# 5_AudioIO.net
KiCad netlist of a schematic drawn in Altium Designer
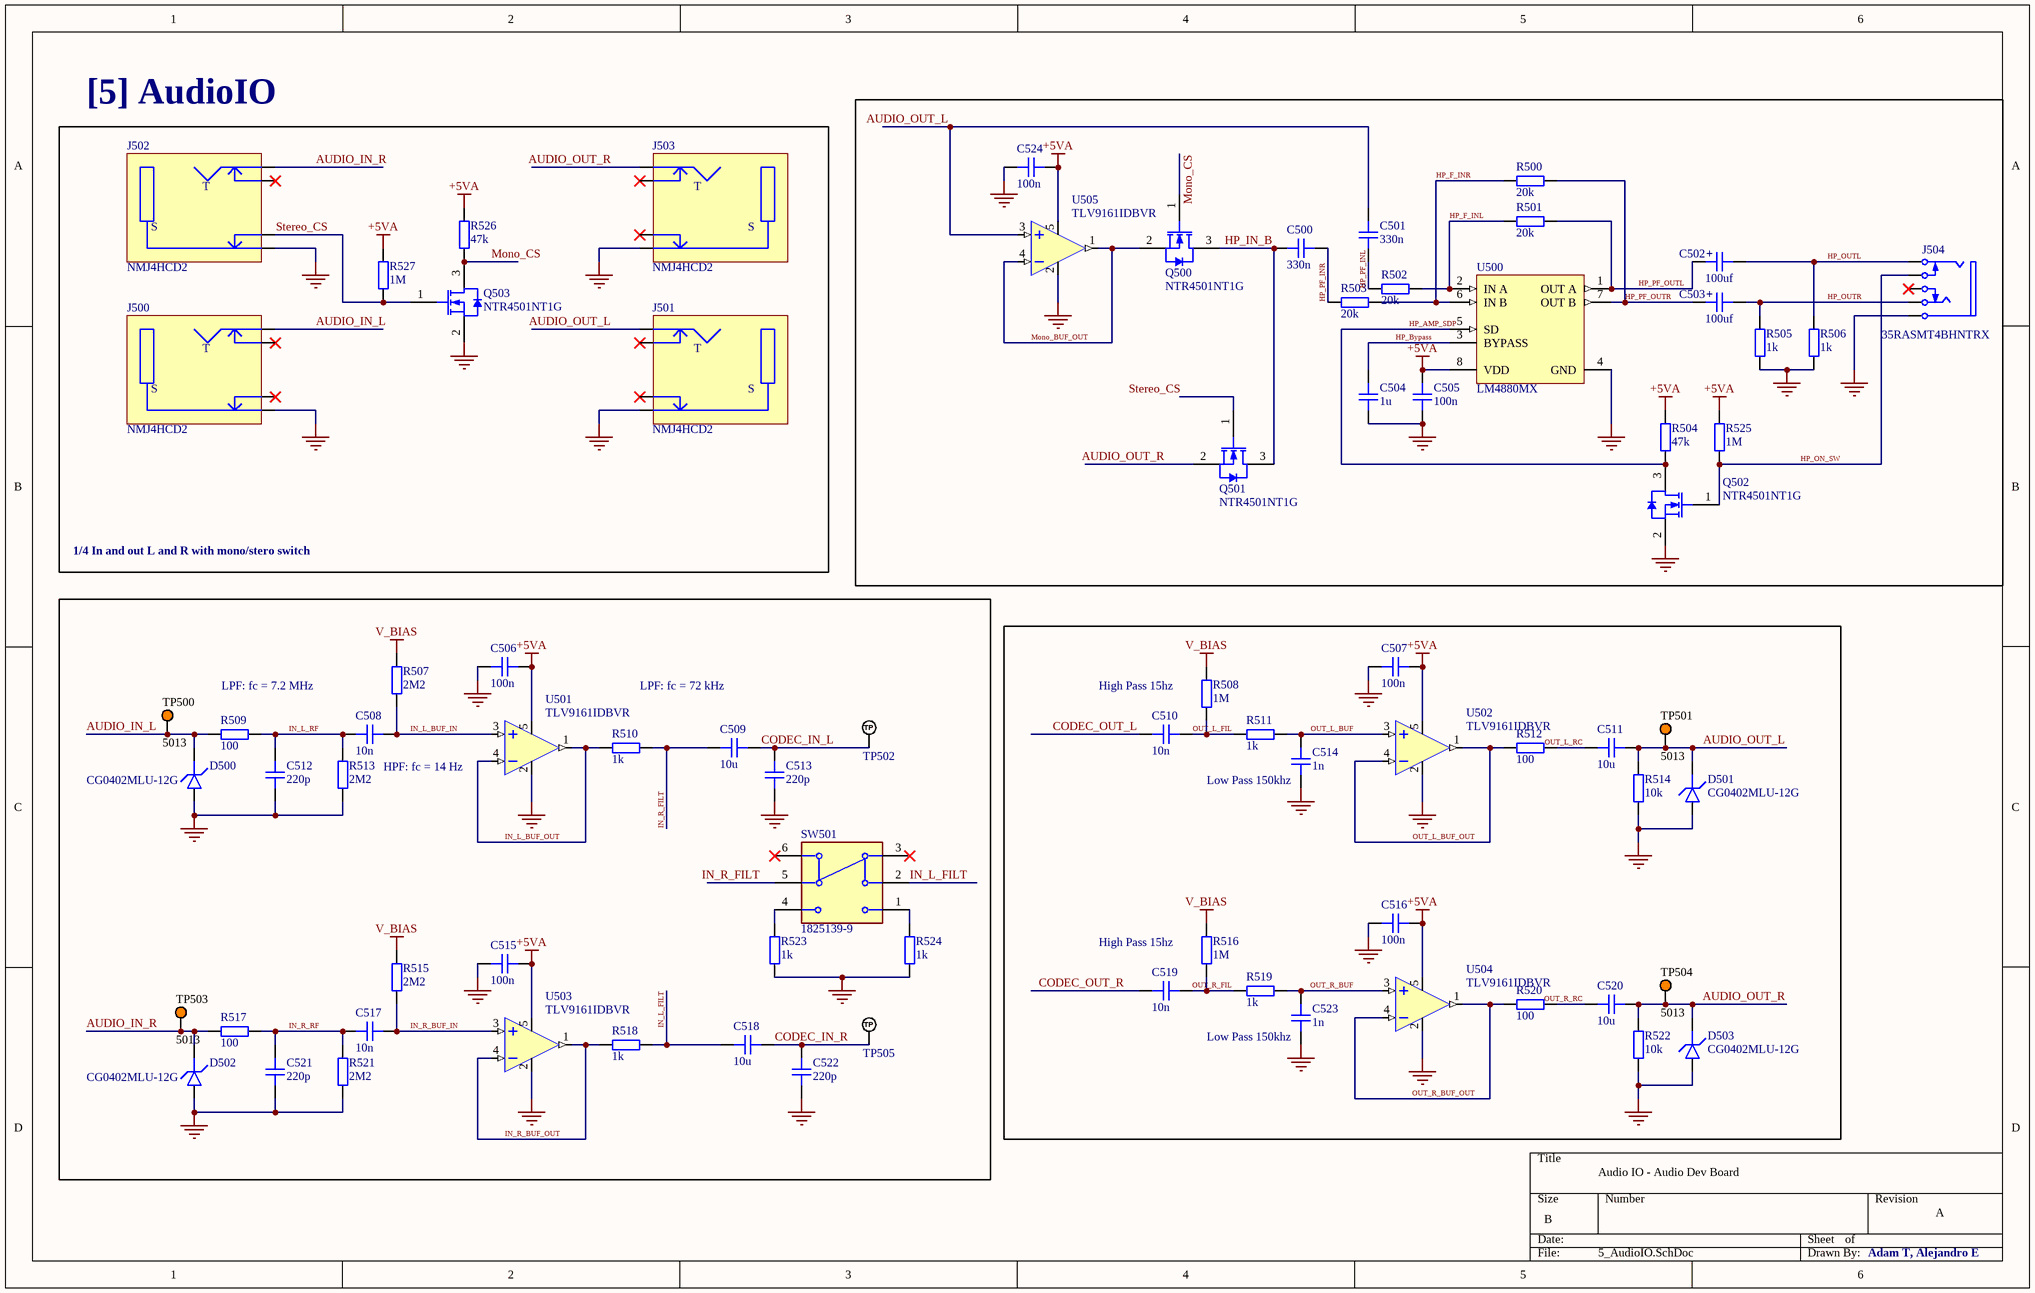
[diagram p0: 5_AudioIO.SchDoc]

(export (version "E")
  (design (tool "Eeschema 10.0.6"))
  (components
    (comp (ref "C500")
      (value "330n")
      (footprint "CAP_0603")
      (description "Capacitor SMD 0603")
      (libsource (lib "Schematic-Lib-PhilsLab") (part "CAP_0603"))
    )
    (comp (ref "C501")
      (value "330n")
      (footprint "CAP_0603")
      (description "Capacitor SMD 0603")
      (libsource (lib "Schematic-Lib-PhilsLab") (part "CAP_0603"))
    )
    (comp (ref "C502")
      (value "100uf")
      (footprint "CAP_AE_SMD_D6MM3_H5M55")
      (description "Capacitor SMD Aluminium Electrolytic 6.3mm Diameter 5.5mm Height\r\nRVT1C101M0605\r\nC37308")
      (libsource (lib "Schematic-Lib-PhilsLab") (part "CAP_ALEL_6.3x5.5"))
    )
    (comp (ref "C503")
      (value "100uf")
      (footprint "CAP_AE_SMD_D6MM3_H5M55")
      (description "Capacitor SMD Aluminium Electrolytic 6.3mm Diameter 5.5mm Height\r\nRVT1C101M0605\r\nC37308")
      (libsource (lib "Schematic-Lib-PhilsLab") (part "CAP_ALEL_6.3x5.5"))
    )
    (comp (ref "C504")
      (value "1u")
      (footprint "CAP_0603")
      (description "Capacitor SMD 0603")
      (libsource (lib "Schematic-Lib-PhilsLab") (part "CAP_0603"))
    )
    (comp (ref "C505")
      (value "100n")
      (footprint "CAP_0402")
      (description "Capacitor SMD 0402")
      (libsource (lib "Schematic-Lib-PhilsLab") (part "CAP_0402"))
    )
    (comp (ref "C506")
      (value "100n")
      (footprint "CAP_0402")
      (description "Capacitor SMD 0402")
      (libsource (lib "Schematic-Lib-PhilsLab") (part "CAP_0402"))
    )
    (comp (ref "C507")
      (value "100n")
      (footprint "CAP_0402")
      (description "Capacitor SMD 0402")
      (libsource (lib "Schematic-Lib-PhilsLab") (part "CAP_0402"))
    )
    (comp (ref "C508")
      (value "10n")
      (footprint "CAP_0402")
      (description "Capacitor SMD 0402")
      (libsource (lib "Schematic-Lib-PhilsLab") (part "CAP_0402"))
    )
    (comp (ref "C509")
      (value "10u")
      (footprint "CAP_0603")
      (description "Capacitor SMD 0603")
      (libsource (lib "Schematic-Lib-PhilsLab") (part "CAP_0603"))
    )
    (comp (ref "C510")
      (value "10n")
      (footprint "CAP_0402")
      (description "Capacitor SMD 0402")
      (libsource (lib "Schematic-Lib-PhilsLab") (part "CAP_0402"))
    )
    (comp (ref "C511")
      (value "10u")
      (footprint "CAP_0603")
      (description "Capacitor SMD 0603")
      (libsource (lib "Schematic-Lib-PhilsLab") (part "CAP_0603"))
    )
    (comp (ref "C512")
      (value "220p")
      (footprint "CAP_0402")
      (description "Capacitor SMD 0402")
      (libsource (lib "Schematic-Lib-PhilsLab") (part "CAP_0402"))
    )
    (comp (ref "C513")
      (value "220p")
      (footprint "CAP_0402")
      (description "Capacitor SMD 0402")
      (libsource (lib "Schematic-Lib-PhilsLab") (part "CAP_0402"))
    )
    (comp (ref "C514")
      (value "1n")
      (footprint "CAP_0402")
      (description "Capacitor SMD 0402")
      (libsource (lib "Schematic-Lib-PhilsLab") (part "CAP_0402"))
    )
    (comp (ref "C515")
      (value "100n")
      (footprint "CAP_0402")
      (description "Capacitor SMD 0402")
      (libsource (lib "Schematic-Lib-PhilsLab") (part "CAP_0402"))
    )
    (comp (ref "C516")
      (value "100n")
      (footprint "CAP_0402")
      (description "Capacitor SMD 0402")
      (libsource (lib "Schematic-Lib-PhilsLab") (part "CAP_0402"))
    )
    (comp (ref "C517")
      (value "10n")
      (footprint "CAP_0402")
      (description "Capacitor SMD 0402")
      (libsource (lib "Schematic-Lib-PhilsLab") (part "CAP_0402"))
    )
    (comp (ref "C518")
      (value "10u")
      (footprint "CAP_0603")
      (description "Capacitor SMD 0603")
      (libsource (lib "Schematic-Lib-PhilsLab") (part "CAP_0603"))
    )
    (comp (ref "C519")
      (value "10n")
      (footprint "CAP_0402")
      (description "Capacitor SMD 0402")
      (libsource (lib "Schematic-Lib-PhilsLab") (part "CAP_0402"))
    )
    (comp (ref "C520")
      (value "10u")
      (footprint "CAP_0603")
      (description "Capacitor SMD 0603")
      (libsource (lib "Schematic-Lib-PhilsLab") (part "CAP_0603"))
    )
    (comp (ref "C521")
      (value "220p")
      (footprint "CAP_0402")
      (description "Capacitor SMD 0402")
      (libsource (lib "Schematic-Lib-PhilsLab") (part "CAP_0402"))
    )
    (comp (ref "C522")
      (value "220p")
      (footprint "CAP_0402")
      (description "Capacitor SMD 0402")
      (libsource (lib "Schematic-Lib-PhilsLab") (part "CAP_0402"))
    )
    (comp (ref "C523")
      (value "1n")
      (footprint "CAP_0402")
      (description "Capacitor SMD 0402")
      (libsource (lib "Schematic-Lib-PhilsLab") (part "CAP_0402"))
    )
    (comp (ref "C524")
      (value "100n")
      (footprint "CAP_0402")
      (description "Capacitor SMD 0402")
      (libsource (lib "Schematic-Lib-PhilsLab") (part "CAP_0402"))
    )
    (comp (ref "D500")
      (value "CG0402MLU-12G")
      (footprint "D_0402")
      (description "Diode TVS / ESD 0402")
      (libsource (lib "Schematic-Lib-PhilsLab") (part "D_TVS_0402"))
    )
    (comp (ref "D501")
      (value "CG0402MLU-12G")
      (footprint "D_0402")
      (description "Diode TVS / ESD 0402")
      (libsource (lib "Schematic-Lib-PhilsLab") (part "D_TVS_0402"))
    )
    (comp (ref "D502")
      (value "CG0402MLU-12G")
      (footprint "D_0402")
      (description "Diode TVS / ESD 0402")
      (libsource (lib "Schematic-Lib-PhilsLab") (part "D_TVS_0402"))
    )
    (comp (ref "D503")
      (value "CG0402MLU-12G")
      (footprint "D_0402")
      (description "Diode TVS / ESD 0402")
      (libsource (lib "Schematic-Lib-PhilsLab") (part "D_TVS_0402"))
    )
    (comp (ref "J500")
      (value "NMJ4HCD2")
      (footprint "NMJ4HCD2")
      (description "1/4\" Mono Jack, TS Switched")
      (fields (field (name "MANUFACTURER") "Neutrik"))
      (libsource (lib "") (part "NMJ4HCD2_1"))
    )
    (comp (ref "J501")
      (value "NMJ4HCD2")
      (footprint "NMJ4HCD2")
      (description "1/4\" Mono Jack, TS Switched")
      (fields (field (name "MANUFACTURER") "Neutrik"))
      (libsource (lib "Schematic-Lib-PhilsLab") (part "NMJ4HCD2"))
    )
    (comp (ref "J502")
      (value "NMJ4HCD2")
      (footprint "NMJ4HCD2")
      (description "1/4\" Mono Jack, TS Switched")
      (fields (field (name "MANUFACTURER") "Neutrik"))
      (libsource (lib "") (part "NMJ4HCD2_1"))
    )
    (comp (ref "J503")
      (value "NMJ4HCD2")
      (footprint "NMJ4HCD2")
      (description "1/4\" Mono Jack, TS Switched")
      (fields (field (name "MANUFACTURER") "Neutrik"))
      (libsource (lib "Schematic-Lib-PhilsLab") (part "NMJ4HCD2"))
    )
    (comp (ref "J504")
      (value "35RASMT4BHNTRX")
      (footprint "SWIT-35RASMT4BHNTRX_V")
      (description "Female 3.5 mm Phone Jack, 5 Position, Height 5 mm, RoHS, Tape and Reel")
      (libsource (lib "Altium Content Vault") (part "JACK-3CD5-RN"))
    )
    (comp (ref "Q500")
      (value "NTR4501NT1G")
      (footprint "ONSC-SOT-23-3-318-08_V")
      (description "Power MOSFET, 20 V, 3.2 A, Single N-Channel, 3-Pin SOT-23, Pb-Free, Tape and Reel")
      (fields (field (name "MANUFACTURER") "On Semiconductor"))
      (libsource (lib "Altium Content Vault") (part "ONSC-NMOS-G1S2D3-3"))
    )
    (comp (ref "Q501")
      (value "NTR4501NT1G")
      (footprint "ONSC-SOT-23-3-318-08_V")
      (description "Power MOSFET, 20 V, 3.2 A, Single N-Channel, 3-Pin SOT-23, Pb-Free, Tape and Reel")
      (fields (field (name "MANUFACTURER") "On Semiconductor"))
      (libsource (lib "Altium Content Vault") (part "ONSC-NMOS-G1S2D3-3"))
    )
    (comp (ref "Q502")
      (value "NTR4501NT1G")
      (footprint "ONSC-SOT-23-3-318-08_V")
      (description "Power MOSFET, 20 V, 3.2 A, Single N-Channel, 3-Pin SOT-23, Pb-Free, Tape and Reel")
      (fields (field (name "MANUFACTURER") "On Semiconductor"))
      (libsource (lib "Altium Content Vault") (part "ONSC-NMOS-G1S2D3-3"))
    )
    (comp (ref "Q503")
      (value "NTR4501NT1G")
      (footprint "ONSC-SOT-23-3-318-08_V")
      (description "Power MOSFET, 20 V, 3.2 A, Single N-Channel, 3-Pin SOT-23, Pb-Free, Tape and Reel")
      (fields (field (name "MANUFACTURER") "On Semiconductor"))
      (libsource (lib "Altium Content Vault") (part "ONSC-NMOS-G1S2D3-3"))
    )
    (comp (ref "R500")
      (value "20k")
      (footprint "RES_0402")
      (description "Resistor SMD 0402")
      (libsource (lib "Schematic-Lib-PhilsLab") (part "RES_0402"))
    )
    (comp (ref "R501")
      (value "20k")
      (footprint "RES_0402")
      (description "Resistor SMD 0402")
      (libsource (lib "Schematic-Lib-PhilsLab") (part "RES_0402"))
    )
    (comp (ref "R502")
      (value "20k")
      (footprint "RES_0402")
      (description "Resistor SMD 0402")
      (libsource (lib "Schematic-Lib-PhilsLab") (part "RES_0402"))
    )
    (comp (ref "R503")
      (value "20k")
      (footprint "RES_0402")
      (description "Resistor SMD 0402")
      (libsource (lib "Schematic-Lib-PhilsLab") (part "RES_0402"))
    )
    (comp (ref "R504")
      (value "47k")
      (footprint "RES_0402")
      (description "Resistor SMD 0402")
      (libsource (lib "Schematic-Lib-PhilsLab") (part "RES_0402"))
    )
    (comp (ref "R505")
      (value "1k")
      (footprint "RES_0402")
      (description "Resistor SMD 0402")
      (libsource (lib "Schematic-Lib-PhilsLab") (part "RES_0402"))
    )
    (comp (ref "R506")
      (value "1k")
      (footprint "RES_0402")
      (description "Resistor SMD 0402")
      (libsource (lib "Schematic-Lib-PhilsLab") (part "RES_0402"))
    )
    (comp (ref "R507")
      (value "2M2")
      (footprint "RES_0402")
      (description "Resistor SMD 0402")
      (libsource (lib "Schematic-Lib-PhilsLab") (part "RES_0402"))
    )
    (comp (ref "R508")
      (value "1M")
      (footprint "RES_0402")
      (description "Resistor SMD 0402")
      (libsource (lib "Schematic-Lib-PhilsLab") (part "RES_0402"))
    )
    (comp (ref "R509")
      (value "100")
      (footprint "RES_0402")
      (description "Resistor SMD 0402")
      (libsource (lib "Schematic-Lib-PhilsLab") (part "RES_0402"))
    )
    (comp (ref "R510")
      (value "1k")
      (footprint "RES_0402")
      (description "Resistor SMD 0402")
      (libsource (lib "Schematic-Lib-PhilsLab") (part "RES_0402"))
    )
    (comp (ref "R511")
      (value "1k")
      (footprint "RES_0402")
      (description "Resistor SMD 0402")
      (libsource (lib "Schematic-Lib-PhilsLab") (part "RES_0402"))
    )
    (comp (ref "R512")
      (value "100")
      (footprint "RES_0402")
      (description "Resistor SMD 0402")
      (libsource (lib "Schematic-Lib-PhilsLab") (part "RES_0402"))
    )
    (comp (ref "R513")
      (value "2M2")
      (footprint "RES_0402")
      (description "Resistor SMD 0402")
      (libsource (lib "Schematic-Lib-PhilsLab") (part "RES_0402"))
    )
    (comp (ref "R514")
      (value "10k")
      (footprint "RES_0402")
      (description "Resistor SMD 0402")
      (libsource (lib "Schematic-Lib-PhilsLab") (part "RES_0402"))
    )
    (comp (ref "R515")
      (value "2M2")
      (footprint "RES_0402")
      (description "Resistor SMD 0402")
      (libsource (lib "Schematic-Lib-PhilsLab") (part "RES_0402"))
    )
    (comp (ref "R516")
      (value "1M")
      (footprint "RES_0402")
      (description "Resistor SMD 0402")
      (libsource (lib "Schematic-Lib-PhilsLab") (part "RES_0402"))
    )
    (comp (ref "R517")
      (value "100")
      (footprint "RES_0402")
      (description "Resistor SMD 0402")
      (libsource (lib "Schematic-Lib-PhilsLab") (part "RES_0402"))
    )
    (comp (ref "R518")
      (value "1k")
      (footprint "RES_0402")
      (description "Resistor SMD 0402")
      (libsource (lib "Schematic-Lib-PhilsLab") (part "RES_0402"))
    )
    (comp (ref "R519")
      (value "1k")
      (footprint "RES_0402")
      (description "Resistor SMD 0402")
      (libsource (lib "Schematic-Lib-PhilsLab") (part "RES_0402"))
    )
    (comp (ref "R520")
      (value "100")
      (footprint "RES_0402")
      (description "Resistor SMD 0402")
      (libsource (lib "Schematic-Lib-PhilsLab") (part "RES_0402"))
    )
    (comp (ref "R521")
      (value "2M2")
      (footprint "RES_0402")
      (description "Resistor SMD 0402")
      (libsource (lib "Schematic-Lib-PhilsLab") (part "RES_0402"))
    )
    (comp (ref "R522")
      (value "10k")
      (footprint "RES_0402")
      (description "Resistor SMD 0402")
      (libsource (lib "Schematic-Lib-PhilsLab") (part "RES_0402"))
    )
    (comp (ref "R523")
      (value "1k")
      (footprint "RES_0402")
      (description "Resistor SMD 0402")
      (libsource (lib "Schematic-Lib-PhilsLab") (part "RES_0402"))
    )
    (comp (ref "R524")
      (value "1k")
      (footprint "RES_0402")
      (description "Resistor SMD 0402")
      (libsource (lib "Schematic-Lib-PhilsLab") (part "RES_0402"))
    )
    (comp (ref "R525")
      (value "1M")
      (footprint "RES_0402")
      (description "Resistor SMD 0402")
      (libsource (lib "Schematic-Lib-PhilsLab") (part "RES_0402"))
    )
    (comp (ref "R526")
      (value "47k")
      (footprint "RES_0402")
      (description "Resistor SMD 0402")
      (libsource (lib "Schematic-Lib-PhilsLab") (part "RES_0402"))
    )
    (comp (ref "R527")
      (value "1M")
      (footprint "RES_0402")
      (description "Resistor SMD 0402")
      (libsource (lib "Schematic-Lib-PhilsLab") (part "RES_0402"))
    )
    (comp (ref "SW501")
      (value "1825139-9")
      (footprint "FP-1825139-9-MFG")
      (description "SWITCH TOGGLE DPDT 5A 120V")
      (libsource (lib "Altium Content Vault") (part "51a017c41a8b71834c976c69ad17c94"))
    )
    (comp (ref "TP500")
      (value "5013")
      (footprint "KSTN-5013_V")
      (description "Test Point, Orange, Through Hole, RoHS, Bulk")
      (fields (field (name "MANUFACTURER") "Keystone"))
      (libsource (lib "Altium Content Vault") (part "TESTPOINT_ORANGE"))
    )
    (comp (ref "TP501")
      (value "5013")
      (footprint "KSTN-5013_V")
      (description "Test Point, Orange, Through Hole, RoHS, Bulk")
      (fields (field (name "MANUFACTURER") "Keystone"))
      (libsource (lib "Altium Content Vault") (part "TESTPOINT_ORANGE"))
    )
    (comp (ref "TP502")
      (value "TP_NOBOM")
      (footprint "PAD_RND_1MM")
      (description "Test Point Round 1mm (NO BOM)")
      (libsource (lib "Schematic-Lib-PhilsLab") (part "TEST_POINT_RND_1MM"))
    )
    (comp (ref "TP503")
      (value "5013")
      (footprint "KSTN-5013_V")
      (description "Test Point, Orange, Through Hole, RoHS, Bulk")
      (fields (field (name "MANUFACTURER") "Keystone"))
      (libsource (lib "Altium Content Vault") (part "TESTPOINT_ORANGE"))
    )
    (comp (ref "TP504")
      (value "5013")
      (footprint "KSTN-5013_V")
      (description "Test Point, Orange, Through Hole, RoHS, Bulk")
      (fields (field (name "MANUFACTURER") "Keystone"))
      (libsource (lib "Altium Content Vault") (part "TESTPOINT_ORANGE"))
    )
    (comp (ref "TP505")
      (value "TP_NOBOM")
      (footprint "PAD_RND_1MM")
      (description "Test Point Round 1mm (NO BOM)")
      (libsource (lib "Schematic-Lib-PhilsLab") (part "TEST_POINT_RND_1MM"))
    )
    (comp (ref "U500")
      (value "LM4880MX")
      (footprint "M08A_L")
      (description "Dual 200mW Audio Power Amplifier with Shutdown Mode, 8-pin Narrow SOIC")
      (fields (field (name "MANUFACTURER") "National Semiconductor"))
      (libsource (lib "Altium Content Vault") (part "AMP-APA-LM4880-8"))
    )
    (comp (ref "U501")
      (value "TLV9161IDBVR")
      (footprint "SOT-23-5")
      (description "TLV916x 16-V, 11-MHz, Rail-to-Rail Input/Output, Low Offset Voltage, Low Noise Op Amp SOT-23-5")
      (fields (field (name "MANUFACTURER") "Texas Instruments"))
      (libsource (lib "Schematic-Lib-PhilsLab") (part "TLV9161IDBVR"))
    )
    (comp (ref "U502")
      (value "TLV9161IDBVR")
      (footprint "SOT-23-5")
      (description "TLV916x 16-V, 11-MHz, Rail-to-Rail Input/Output, Low Offset Voltage, Low Noise Op Amp SOT-23-5")
      (fields (field (name "MANUFACTURER") "Texas Instruments"))
      (libsource (lib "Schematic-Lib-PhilsLab") (part "TLV9161IDBVR"))
    )
    (comp (ref "U503")
      (value "TLV9161IDBVR")
      (footprint "SOT-23-5")
      (description "TLV916x 16-V, 11-MHz, Rail-to-Rail Input/Output, Low Offset Voltage, Low Noise Op Amp SOT-23-5")
      (fields (field (name "MANUFACTURER") "Texas Instruments"))
      (libsource (lib "Schematic-Lib-PhilsLab") (part "TLV9161IDBVR"))
    )
    (comp (ref "U504")
      (value "TLV9161IDBVR")
      (footprint "SOT-23-5")
      (description "TLV916x 16-V, 11-MHz, Rail-to-Rail Input/Output, Low Offset Voltage, Low Noise Op Amp SOT-23-5")
      (fields (field (name "MANUFACTURER") "Texas Instruments"))
      (libsource (lib "Schematic-Lib-PhilsLab") (part "TLV9161IDBVR"))
    )
    (comp (ref "U505")
      (value "TLV9161IDBVR")
      (footprint "SOT-23-5")
      (description "TLV916x 16-V, 11-MHz, Rail-to-Rail Input/Output, Low Offset Voltage, Low Noise Op Amp SOT-23-5")
      (fields (field (name "MANUFACTURER") "Texas Instruments"))
      (libsource (lib "Schematic-Lib-PhilsLab") (part "TLV9161IDBVR"))
    )
  )
  (nets
    (net (code "1") (name "+5VA") (class "Default")
      (node (ref "C505") (pin "2") (pinfunction "2_2") (pintype "passive"))
      (node (ref "C506") (pin "2") (pinfunction "2_2") (pintype "passive"))
      (node (ref "C507") (pin "2") (pinfunction "2_2") (pintype "passive"))
      (node (ref "C515") (pin "2") (pinfunction "2_2") (pintype "passive"))
      (node (ref "C516") (pin "2") (pinfunction "2_2") (pintype "passive"))
      (node (ref "C524") (pin "2") (pinfunction "2_2") (pintype "passive"))
      (node (ref "R504") (pin "2") (pinfunction "2_2") (pintype "passive"))
      (node (ref "R525") (pin "2") (pinfunction "2_2") (pintype "passive"))
      (node (ref "R526") (pin "1") (pinfunction "1_1") (pintype "passive"))
      (node (ref "R527") (pin "1") (pinfunction "1_1") (pintype "passive"))
      (node (ref "U500") (pin "8") (pinfunction "VDD_8") (pintype "power_in"))
      (node (ref "U501") (pin "5") (pinfunction "V+_5") (pintype "passive"))
      (node (ref "U502") (pin "5") (pinfunction "V+_5") (pintype "passive"))
      (node (ref "U503") (pin "5") (pinfunction "V+_5") (pintype "passive"))
      (node (ref "U504") (pin "5") (pinfunction "V+_5") (pintype "passive"))
      (node (ref "U505") (pin "5") (pinfunction "V+_5") (pintype "passive"))
    )
    (net (code "2") (name "/AUDIO_IN_L") (class "Default")
      (node (ref "D500") (pin "K") (pinfunction "K_K") (pintype "passive"))
      (node (ref "J500") (pin "T") (pinfunction "T_T") (pintype "passive"))
      (node (ref "R509") (pin "1") (pinfunction "1_1") (pintype "passive"))
      (node (ref "TP500") (pin "1") (pinfunction "1_1") (pintype "passive"))
    )
    (net (code "3") (name "/AUDIO_IN_R") (class "Default")
      (node (ref "D502") (pin "K") (pinfunction "K_K") (pintype "passive"))
      (node (ref "J502") (pin "T") (pinfunction "T_T") (pintype "passive"))
      (node (ref "R517") (pin "1") (pinfunction "1_1") (pintype "passive"))
      (node (ref "TP503") (pin "1") (pinfunction "1_1") (pintype "passive"))
    )
    (net (code "4") (name "/AUDIO_OUT_L") (class "Default")
      (node (ref "C501") (pin "1") (pinfunction "1_1") (pintype "passive"))
      (node (ref "C511") (pin "2") (pinfunction "2_2") (pintype "passive"))
      (node (ref "D501") (pin "K") (pinfunction "K_K") (pintype "passive"))
      (node (ref "J501") (pin "T") (pinfunction "T_T") (pintype "passive"))
      (node (ref "R514") (pin "1") (pinfunction "1_1") (pintype "passive"))
      (node (ref "TP501") (pin "1") (pinfunction "1_1") (pintype "passive"))
      (node (ref "U505") (pin "3") (pinfunction "IN+_3") (pintype "input"))
    )
    (net (code "5") (name "/AUDIO_OUT_R") (class "Default")
      (node (ref "C520") (pin "2") (pinfunction "2_2") (pintype "passive"))
      (node (ref "D503") (pin "K") (pinfunction "K_K") (pintype "passive"))
      (node (ref "J503") (pin "T") (pinfunction "T_T") (pintype "passive"))
      (node (ref "Q501") (pin "2") (pinfunction "S_2") (pintype "passive"))
      (node (ref "R522") (pin "1") (pinfunction "1_1") (pintype "passive"))
      (node (ref "TP504") (pin "1") (pinfunction "1_1") (pintype "passive"))
    )
    (net (code "6") (name "/CODEC_IN_L") (class "Default")
      (node (ref "C509") (pin "1") (pinfunction "1_1") (pintype "passive"))
      (node (ref "C513") (pin "2") (pinfunction "2_2") (pintype "passive"))
      (node (ref "TP502") (pin "1") (pinfunction "TP_1") (pintype "passive"))
    )
    (net (code "7") (name "/CODEC_IN_R") (class "Default")
      (node (ref "C518") (pin "1") (pinfunction "1_1") (pintype "passive"))
      (node (ref "C522") (pin "2") (pinfunction "2_2") (pintype "passive"))
      (node (ref "TP505") (pin "1") (pinfunction "TP_1") (pintype "passive"))
    )
    (net (code "8") (name "/CODEC_OUT_L") (class "Default")
      (node (ref "C510") (pin "1") (pinfunction "1_1") (pintype "passive"))
    )
    (net (code "9") (name "/CODEC_OUT_R") (class "Default")
      (node (ref "C519") (pin "1") (pinfunction "1_1") (pintype "passive"))
    )
    (net (code "10") (name "/HP_AMP_SDP") (class "Default")
      (node (ref "Q502") (pin "3") (pinfunction "D_3") (pintype "passive"))
      (node (ref "R504") (pin "1") (pinfunction "1_1") (pintype "passive"))
      (node (ref "U500") (pin "5") (pinfunction "SD_5") (pintype "input"))
    )
    (net (code "11") (name "/HP_Bypass") (class "Default")
      (node (ref "C504") (pin "2") (pinfunction "2_2") (pintype "passive"))
      (node (ref "U500") (pin "3") (pinfunction "BYPASS_3") (pintype "passive"))
    )
    (net (code "12") (name "/HP_F_INL") (class "Default")
      (node (ref "R501") (pin "1") (pinfunction "1_1") (pintype "passive"))
      (node (ref "R502") (pin "2") (pinfunction "2_2") (pintype "passive"))
      (node (ref "U500") (pin "2") (pinfunction "IN_A_2") (pintype "input"))
    )
    (net (code "13") (name "/HP_F_INR") (class "Default")
      (node (ref "R500") (pin "1") (pinfunction "1_1") (pintype "passive"))
      (node (ref "R503") (pin "2") (pinfunction "2_2") (pintype "passive"))
      (node (ref "U500") (pin "6") (pinfunction "IN_B_6") (pintype "input"))
    )
    (net (code "14") (name "/HP_IN_B") (class "Default")
      (node (ref "C500") (pin "2") (pinfunction "2_2") (pintype "passive"))
      (node (ref "Q500") (pin "3") (pinfunction "D_3") (pintype "passive"))
      (node (ref "Q501") (pin "3") (pinfunction "D_3") (pintype "passive"))
    )
    (net (code "15") (name "/HP_ON_SW") (class "Default")
      (node (ref "J504") (pin "4") (pinfunction "4_4") (pintype "passive"))
      (node (ref "Q502") (pin "1") (pinfunction "G_1") (pintype "passive"))
      (node (ref "R525") (pin "1") (pinfunction "1_1") (pintype "passive"))
    )
    (net (code "16") (name "/HP_OUTL") (class "Default")
      (node (ref "C502") (pin "2") (pinfunction "2_2") (pintype "passive"))
      (node (ref "J504") (pin "2") (pinfunction "2_2") (pintype "passive"))
      (node (ref "R506") (pin "2") (pinfunction "2_2") (pintype "passive"))
    )
    (net (code "17") (name "/HP_OUTR") (class "Default")
      (node (ref "C503") (pin "2") (pinfunction "2_2") (pintype "passive"))
      (node (ref "J504") (pin "3") (pinfunction "3_3") (pintype "passive"))
      (node (ref "R505") (pin "2") (pinfunction "2_2") (pintype "passive"))
    )
    (net (code "18") (name "/HP_PF_INL") (class "Default")
      (node (ref "C501") (pin "2") (pinfunction "2_2") (pintype "passive"))
      (node (ref "R502") (pin "1") (pinfunction "1_1") (pintype "passive"))
    )
    (net (code "19") (name "/HP_PF_INR") (class "Default")
      (node (ref "C500") (pin "1") (pinfunction "1_1") (pintype "passive"))
      (node (ref "R503") (pin "1") (pinfunction "1_1") (pintype "passive"))
    )
    (net (code "20") (name "/HP_PF_OUTL") (class "Default")
      (node (ref "C502") (pin "1") (pinfunction "1_1") (pintype "passive"))
      (node (ref "R501") (pin "2") (pinfunction "2_2") (pintype "passive"))
      (node (ref "U500") (pin "1") (pinfunction "OUT_A_1") (pintype "output"))
    )
    (net (code "21") (name "/HP_PF_OUTR") (class "Default")
      (node (ref "C503") (pin "1") (pinfunction "1_1") (pintype "passive"))
      (node (ref "R500") (pin "2") (pinfunction "2_2") (pintype "passive"))
      (node (ref "U500") (pin "7") (pinfunction "OUT_B_7") (pintype "output"))
    )
    (net (code "22") (name "/IN_L_BUF_IN") (class "Default")
      (node (ref "C508") (pin "2") (pinfunction "2_2") (pintype "passive"))
      (node (ref "R507") (pin "1") (pinfunction "1_1") (pintype "passive"))
      (node (ref "U501") (pin "3") (pinfunction "IN+_3") (pintype "input"))
    )
    (net (code "23") (name "/IN_L_BUF_OUT") (class "Default")
      (node (ref "R510") (pin "1") (pinfunction "1_1") (pintype "passive"))
      (node (ref "U501") (pin "1") (pinfunction "OUT_1") (pintype "output"))
      (node (ref "U501") (pin "4") (pinfunction "IN-_4") (pintype "input"))
    )
    (net (code "24") (name "/IN_L_FILT") (class "Default")
      (node (ref "C518") (pin "2") (pinfunction "2_2") (pintype "passive"))
      (node (ref "R518") (pin "2") (pinfunction "2_2") (pintype "passive"))
      (node (ref "SW501") (pin "2") (pinfunction "2_2") (pintype "passive"))
    )
    (net (code "25") (name "/IN_L_RF") (class "Default")
      (node (ref "C508") (pin "1") (pinfunction "1_1") (pintype "passive"))
      (node (ref "C512") (pin "2") (pinfunction "2_2") (pintype "passive"))
      (node (ref "R509") (pin "2") (pinfunction "2_2") (pintype "passive"))
      (node (ref "R513") (pin "2") (pinfunction "2_2") (pintype "passive"))
    )
    (net (code "26") (name "/IN_R_BUF_IN") (class "Default")
      (node (ref "C517") (pin "2") (pinfunction "2_2") (pintype "passive"))
      (node (ref "R515") (pin "1") (pinfunction "1_1") (pintype "passive"))
      (node (ref "U503") (pin "3") (pinfunction "IN+_3") (pintype "input"))
    )
    (net (code "27") (name "/IN_R_BUF_OUT") (class "Default")
      (node (ref "R518") (pin "1") (pinfunction "1_1") (pintype "passive"))
      (node (ref "U503") (pin "1") (pinfunction "OUT_1") (pintype "output"))
      (node (ref "U503") (pin "4") (pinfunction "IN-_4") (pintype "input"))
    )
    (net (code "28") (name "/IN_R_FILT") (class "Default")
      (node (ref "C509") (pin "2") (pinfunction "2_2") (pintype "passive"))
      (node (ref "R510") (pin "2") (pinfunction "2_2") (pintype "passive"))
      (node (ref "SW501") (pin "5") (pinfunction "5_5") (pintype "passive"))
    )
    (net (code "29") (name "/IN_R_RF") (class "Default")
      (node (ref "C517") (pin "1") (pinfunction "1_1") (pintype "passive"))
      (node (ref "C521") (pin "2") (pinfunction "2_2") (pintype "passive"))
      (node (ref "R517") (pin "2") (pinfunction "2_2") (pintype "passive"))
      (node (ref "R521") (pin "2") (pinfunction "2_2") (pintype "passive"))
    )
    (net (code "30") (name "/Mono_BUF_OUT") (class "Default")
      (node (ref "Q500") (pin "2") (pinfunction "S_2") (pintype "passive"))
      (node (ref "U505") (pin "1") (pinfunction "OUT_1") (pintype "output"))
      (node (ref "U505") (pin "4") (pinfunction "IN-_4") (pintype "input"))
    )
    (net (code "31") (name "/Mono_CS") (class "Default")
      (node (ref "Q500") (pin "1") (pinfunction "G_1") (pintype "passive"))
      (node (ref "Q503") (pin "3") (pinfunction "D_3") (pintype "passive"))
      (node (ref "R526") (pin "2") (pinfunction "2_2") (pintype "passive"))
    )
    (net (code "32") (name "/OUT_L_BUF") (class "Default")
      (node (ref "C514") (pin "2") (pinfunction "2_2") (pintype "passive"))
      (node (ref "R511") (pin "1") (pinfunction "1_1") (pintype "passive"))
      (node (ref "U502") (pin "3") (pinfunction "IN+_3") (pintype "input"))
    )
    (net (code "33") (name "/OUT_L_BUF_OUT") (class "Default")
      (node (ref "R512") (pin "2") (pinfunction "2_2") (pintype "passive"))
      (node (ref "U502") (pin "1") (pinfunction "OUT_1") (pintype "output"))
      (node (ref "U502") (pin "4") (pinfunction "IN-_4") (pintype "input"))
    )
    (net (code "34") (name "/OUT_L_FIL") (class "Default")
      (node (ref "C510") (pin "2") (pinfunction "2_2") (pintype "passive"))
      (node (ref "R508") (pin "1") (pinfunction "1_1") (pintype "passive"))
      (node (ref "R511") (pin "2") (pinfunction "2_2") (pintype "passive"))
    )
    (net (code "35") (name "/OUT_L_RC") (class "Default")
      (node (ref "C511") (pin "1") (pinfunction "1_1") (pintype "passive"))
      (node (ref "R512") (pin "1") (pinfunction "1_1") (pintype "passive"))
    )
    (net (code "36") (name "/OUT_R_BUF") (class "Default")
      (node (ref "C523") (pin "2") (pinfunction "2_2") (pintype "passive"))
      (node (ref "R519") (pin "1") (pinfunction "1_1") (pintype "passive"))
      (node (ref "U504") (pin "3") (pinfunction "IN+_3") (pintype "input"))
    )
    (net (code "37") (name "/OUT_R_BUF_OUT") (class "Default")
      (node (ref "R520") (pin "2") (pinfunction "2_2") (pintype "passive"))
      (node (ref "U504") (pin "1") (pinfunction "OUT_1") (pintype "output"))
      (node (ref "U504") (pin "4") (pinfunction "IN-_4") (pintype "input"))
    )
    (net (code "38") (name "/OUT_R_FIL") (class "Default")
      (node (ref "C519") (pin "2") (pinfunction "2_2") (pintype "passive"))
      (node (ref "R516") (pin "1") (pinfunction "1_1") (pintype "passive"))
      (node (ref "R519") (pin "2") (pinfunction "2_2") (pintype "passive"))
    )
    (net (code "39") (name "/OUT_R_RC") (class "Default")
      (node (ref "C520") (pin "1") (pinfunction "1_1") (pintype "passive"))
      (node (ref "R520") (pin "1") (pinfunction "1_1") (pintype "passive"))
    )
    (net (code "40") (name "/Stereo_CS") (class "Default")
      (node (ref "J502") (pin "SN") (pinfunction "SN_SN") (pintype "passive"))
      (node (ref "Q501") (pin "1") (pinfunction "G_1") (pintype "passive"))
      (node (ref "Q503") (pin "1") (pinfunction "G_1") (pintype "passive"))
      (node (ref "R527") (pin "2") (pinfunction "2_2") (pintype "passive"))
    )
    (net (code "41") (name "GND") (class "Default")
      (node (ref "C504") (pin "1") (pinfunction "1_1") (pintype "passive"))
      (node (ref "C505") (pin "1") (pinfunction "1_1") (pintype "passive"))
      (node (ref "C506") (pin "1") (pinfunction "1_1") (pintype "passive"))
      (node (ref "C507") (pin "1") (pinfunction "1_1") (pintype "passive"))
      (node (ref "C512") (pin "1") (pinfunction "1_1") (pintype "passive"))
      (node (ref "C513") (pin "1") (pinfunction "1_1") (pintype "passive"))
      (node (ref "C514") (pin "1") (pinfunction "1_1") (pintype "passive"))
      (node (ref "C515") (pin "1") (pinfunction "1_1") (pintype "passive"))
      (node (ref "C516") (pin "1") (pinfunction "1_1") (pintype "passive"))
      (node (ref "C521") (pin "1") (pinfunction "1_1") (pintype "passive"))
      (node (ref "C522") (pin "1") (pinfunction "1_1") (pintype "passive"))
      (node (ref "C523") (pin "1") (pinfunction "1_1") (pintype "passive"))
      (node (ref "C524") (pin "1") (pinfunction "1_1") (pintype "passive"))
      (node (ref "D500") (pin "A") (pinfunction "A_A") (pintype "passive"))
      (node (ref "D501") (pin "A") (pinfunction "A_A") (pintype "passive"))
      (node (ref "D502") (pin "A") (pinfunction "A_A") (pintype "passive"))
      (node (ref "D503") (pin "A") (pinfunction "A_A") (pintype "passive"))
      (node (ref "J500") (pin "S") (pinfunction "S_S") (pintype "passive"))
      (node (ref "J501") (pin "S") (pinfunction "S_S") (pintype "passive"))
      (node (ref "J502") (pin "S") (pinfunction "S_S") (pintype "passive"))
      (node (ref "J503") (pin "S") (pinfunction "S_S") (pintype "passive"))
      (node (ref "J504") (pin "1") (pinfunction "1_1") (pintype "passive"))
      (node (ref "Q502") (pin "2") (pinfunction "S_2") (pintype "passive"))
      (node (ref "Q503") (pin "2") (pinfunction "S_2") (pintype "passive"))
      (node (ref "R505") (pin "1") (pinfunction "1_1") (pintype "passive"))
      (node (ref "R506") (pin "1") (pinfunction "1_1") (pintype "passive"))
      (node (ref "R513") (pin "1") (pinfunction "1_1") (pintype "passive"))
      (node (ref "R514") (pin "2") (pinfunction "2_2") (pintype "passive"))
      (node (ref "R521") (pin "1") (pinfunction "1_1") (pintype "passive"))
      (node (ref "R522") (pin "2") (pinfunction "2_2") (pintype "passive"))
      (node (ref "R523") (pin "1") (pinfunction "1_1") (pintype "passive"))
      (node (ref "R524") (pin "1") (pinfunction "1_1") (pintype "passive"))
      (node (ref "U500") (pin "4") (pinfunction "GND_4") (pintype "power_in"))
      (node (ref "U501") (pin "2") (pinfunction "V-_2") (pintype "passive"))
      (node (ref "U502") (pin "2") (pinfunction "V-_2") (pintype "passive"))
      (node (ref "U503") (pin "2") (pinfunction "V-_2") (pintype "passive"))
      (node (ref "U504") (pin "2") (pinfunction "V-_2") (pintype "passive"))
      (node (ref "U505") (pin "2") (pinfunction "V-_2") (pintype "passive"))
    )
    (net (code "42") (name "Net-(R523-Pad2)") (class "Default")
      (node (ref "R523") (pin "2") (pinfunction "2_2") (pintype "passive"))
      (node (ref "SW501") (pin "4") (pinfunction "4_4") (pintype "passive"))
    )
    (net (code "43") (name "Net-(R524-Pad2)") (class "Default")
      (node (ref "R524") (pin "2") (pinfunction "2_2") (pintype "passive"))
      (node (ref "SW501") (pin "1") (pinfunction "1_1") (pintype "passive"))
    )
    (net (code "44") (name "V_BIAS") (class "Default")
      (node (ref "R507") (pin "2") (pinfunction "2_2") (pintype "passive"))
      (node (ref "R508") (pin "2") (pinfunction "2_2") (pintype "passive"))
      (node (ref "R515") (pin "2") (pinfunction "2_2") (pintype "passive"))
      (node (ref "R516") (pin "2") (pinfunction "2_2") (pintype "passive"))
    )
    (net (code "45") (name "unconnected-(J500-PadSN)") (class "Default")
      (node (ref "J500") (pin "SN") (pinfunction "SN_SN") (pintype "passive+no_connect"))
    )
    (net (code "46") (name "unconnected-(J500-PadTN)") (class "Default")
      (node (ref "J500") (pin "TN") (pinfunction "TN_TN") (pintype "passive+no_connect"))
    )
    (net (code "47") (name "unconnected-(J501-PadSN)") (class "Default")
      (node (ref "J501") (pin "SN") (pinfunction "SN_SN") (pintype "passive+no_connect"))
    )
    (net (code "48") (name "unconnected-(J501-PadTN)") (class "Default")
      (node (ref "J501") (pin "TN") (pinfunction "TN_TN") (pintype "passive+no_connect"))
    )
    (net (code "49") (name "unconnected-(J502-PadTN)") (class "Default")
      (node (ref "J502") (pin "TN") (pinfunction "TN_TN") (pintype "passive+no_connect"))
    )
    (net (code "50") (name "unconnected-(J503-PadSN)") (class "Default")
      (node (ref "J503") (pin "SN") (pinfunction "SN_SN") (pintype "passive+no_connect"))
    )
    (net (code "51") (name "unconnected-(J503-PadTN)") (class "Default")
      (node (ref "J503") (pin "TN") (pinfunction "TN_TN") (pintype "passive+no_connect"))
    )
    (net (code "52") (name "unconnected-(J504-Pad5)") (class "Default")
      (node (ref "J504") (pin "5") (pinfunction "5_5") (pintype "passive+no_connect"))
    )
    (net (code "53") (name "unconnected-(SW501-Pad3)") (class "Default")
      (node (ref "SW501") (pin "3") (pinfunction "3_3") (pintype "passive+no_connect"))
    )
    (net (code "54") (name "unconnected-(SW501-Pad6)") (class "Default")
      (node (ref "SW501") (pin "6") (pinfunction "6_6") (pintype "passive+no_connect"))
    )
  )
)
